# micro.net
KiCad netlist of a schematic drawn in Altium Designer
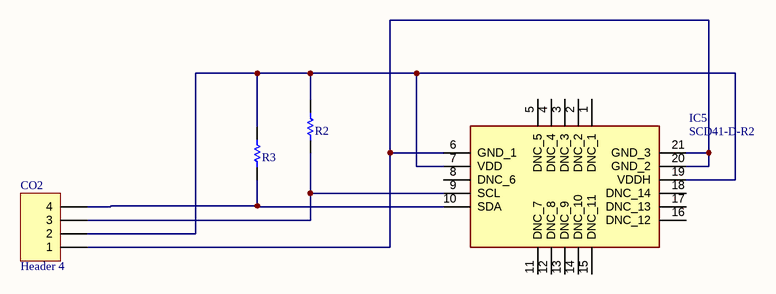
[diagram p0: micro.SchDoc]

(export (version "E")
  (design (tool "Eeschema 10.0.6"))
  (components
    (comp (ref "CO2")
      (value "Header 4")
      (footprint "HDR1X4")
      (description "Header, 4-Pin")
      (fields (field (name "PUBLISHER") "Altium Limited"))
      (libsource (lib "Miscellaneous Connectors") (part "Header 4"))
    )
    (comp (ref "IC5")
      (value "SCD41-D-R2")
      (footprint "SamacSys:SCD41DR2")
      (description "Integrated Circuit")
      (fields (field (name "MOUSER PART NUMBER") "403-SCD41-D-R2"))
      (libsource (lib "*") (part "SCD41-D-R2"))
    )
    (comp (ref "R2")
      (value "ERA3AEB1131V")
      (footprint "RESC1608X55X30ML20T20")
      (fields (field (name "MANUFACTURER") "Panasonic"))
      (libsource (lib "Altium Content Vault") (part "RES"))
    )
    (comp (ref "R3")
      (value "ERA3AEB1131V")
      (footprint "RESC1608X55X30ML20T20")
      (fields (field (name "MANUFACTURER") "Panasonic"))
      (libsource (lib "Altium Content Vault") (part "RES"))
    )
  )
  (nets
    (net (code "1") (name "Net-(IC5-GND_1)") (class "Default")
      (node (ref "CO2") (pin "1") (pinfunction "1_1") (pintype "passive"))
      (node (ref "IC5") (pin "20") (pinfunction "GND_2_20") (pintype "passive"))
      (node (ref "IC5") (pin "21") (pinfunction "GND_3_21") (pintype "passive"))
      (node (ref "IC5") (pin "6") (pinfunction "GND_1_6") (pintype "passive"))
    )
    (net (code "2") (name "Net-(IC5-SCL)") (class "Default")
      (node (ref "CO2") (pin "3") (pinfunction "3_3") (pintype "passive"))
      (node (ref "IC5") (pin "9") (pinfunction "SCL_9") (pintype "passive"))
      (node (ref "R2") (pin "2") (pinfunction "2_2") (pintype "passive"))
    )
    (net (code "3") (name "Net-(IC5-SDA)") (class "Default")
      (node (ref "CO2") (pin "4") (pinfunction "4_4") (pintype "passive"))
      (node (ref "IC5") (pin "10") (pinfunction "SDA_10") (pintype "passive"))
      (node (ref "R3") (pin "2") (pinfunction "2_2") (pintype "passive"))
    )
    (net (code "4") (name "Net-(IC5-VDD)") (class "Default")
      (node (ref "CO2") (pin "2") (pinfunction "2_2") (pintype "passive"))
      (node (ref "IC5") (pin "19") (pinfunction "VDDH_19") (pintype "passive"))
      (node (ref "IC5") (pin "7") (pinfunction "VDD_7") (pintype "passive"))
      (node (ref "R2") (pin "1") (pinfunction "1_1") (pintype "passive"))
      (node (ref "R3") (pin "1") (pinfunction "1_1") (pintype "passive"))
    )
    (net (code "5") (name "unconnected-(IC5-DNC_1-Pad1)") (class "Default")
      (node (ref "IC5") (pin "1") (pinfunction "DNC_1_1") (pintype "passive"))
    )
    (net (code "6") (name "unconnected-(IC5-DNC_2-Pad2)") (class "Default")
      (node (ref "IC5") (pin "2") (pinfunction "DNC_2_2") (pintype "passive"))
    )
    (net (code "7") (name "unconnected-(IC5-DNC_3-Pad3)") (class "Default")
      (node (ref "IC5") (pin "3") (pinfunction "DNC_3_3") (pintype "passive"))
    )
    (net (code "8") (name "unconnected-(IC5-DNC_4-Pad4)") (class "Default")
      (node (ref "IC5") (pin "4") (pinfunction "DNC_4_4") (pintype "passive"))
    )
    (net (code "9") (name "unconnected-(IC5-DNC_5-Pad5)") (class "Default")
      (node (ref "IC5") (pin "5") (pinfunction "DNC_5_5") (pintype "passive"))
    )
    (net (code "10") (name "unconnected-(IC5-DNC_6-Pad8)") (class "Default")
      (node (ref "IC5") (pin "8") (pinfunction "DNC_6_8") (pintype "passive"))
    )
    (net (code "11") (name "unconnected-(IC5-DNC_7-Pad11)") (class "Default")
      (node (ref "IC5") (pin "11") (pinfunction "DNC_7_11") (pintype "passive"))
    )
    (net (code "12") (name "unconnected-(IC5-DNC_8-Pad12)") (class "Default")
      (node (ref "IC5") (pin "12") (pinfunction "DNC_8_12") (pintype "passive"))
    )
    (net (code "13") (name "unconnected-(IC5-DNC_9-Pad13)") (class "Default")
      (node (ref "IC5") (pin "13") (pinfunction "DNC_9_13") (pintype "passive"))
    )
    (net (code "14") (name "unconnected-(IC5-DNC_10-Pad14)") (class "Default")
      (node (ref "IC5") (pin "14") (pinfunction "DNC_10_14") (pintype "passive"))
    )
    (net (code "15") (name "unconnected-(IC5-DNC_11-Pad15)") (class "Default")
      (node (ref "IC5") (pin "15") (pinfunction "DNC_11_15") (pintype "passive"))
    )
    (net (code "16") (name "unconnected-(IC5-DNC_12-Pad16)") (class "Default")
      (node (ref "IC5") (pin "16") (pinfunction "DNC_12_16") (pintype "passive"))
    )
    (net (code "17") (name "unconnected-(IC5-DNC_13-Pad17)") (class "Default")
      (node (ref "IC5") (pin "17") (pinfunction "DNC_13_17") (pintype "passive"))
    )
    (net (code "18") (name "unconnected-(IC5-DNC_14-Pad18)") (class "Default")
      (node (ref "IC5") (pin "18") (pinfunction "DNC_14_18") (pintype "passive"))
    )
  )
)
